# CHARGING.net
KiCad netlist of a schematic drawn in Altium Designer
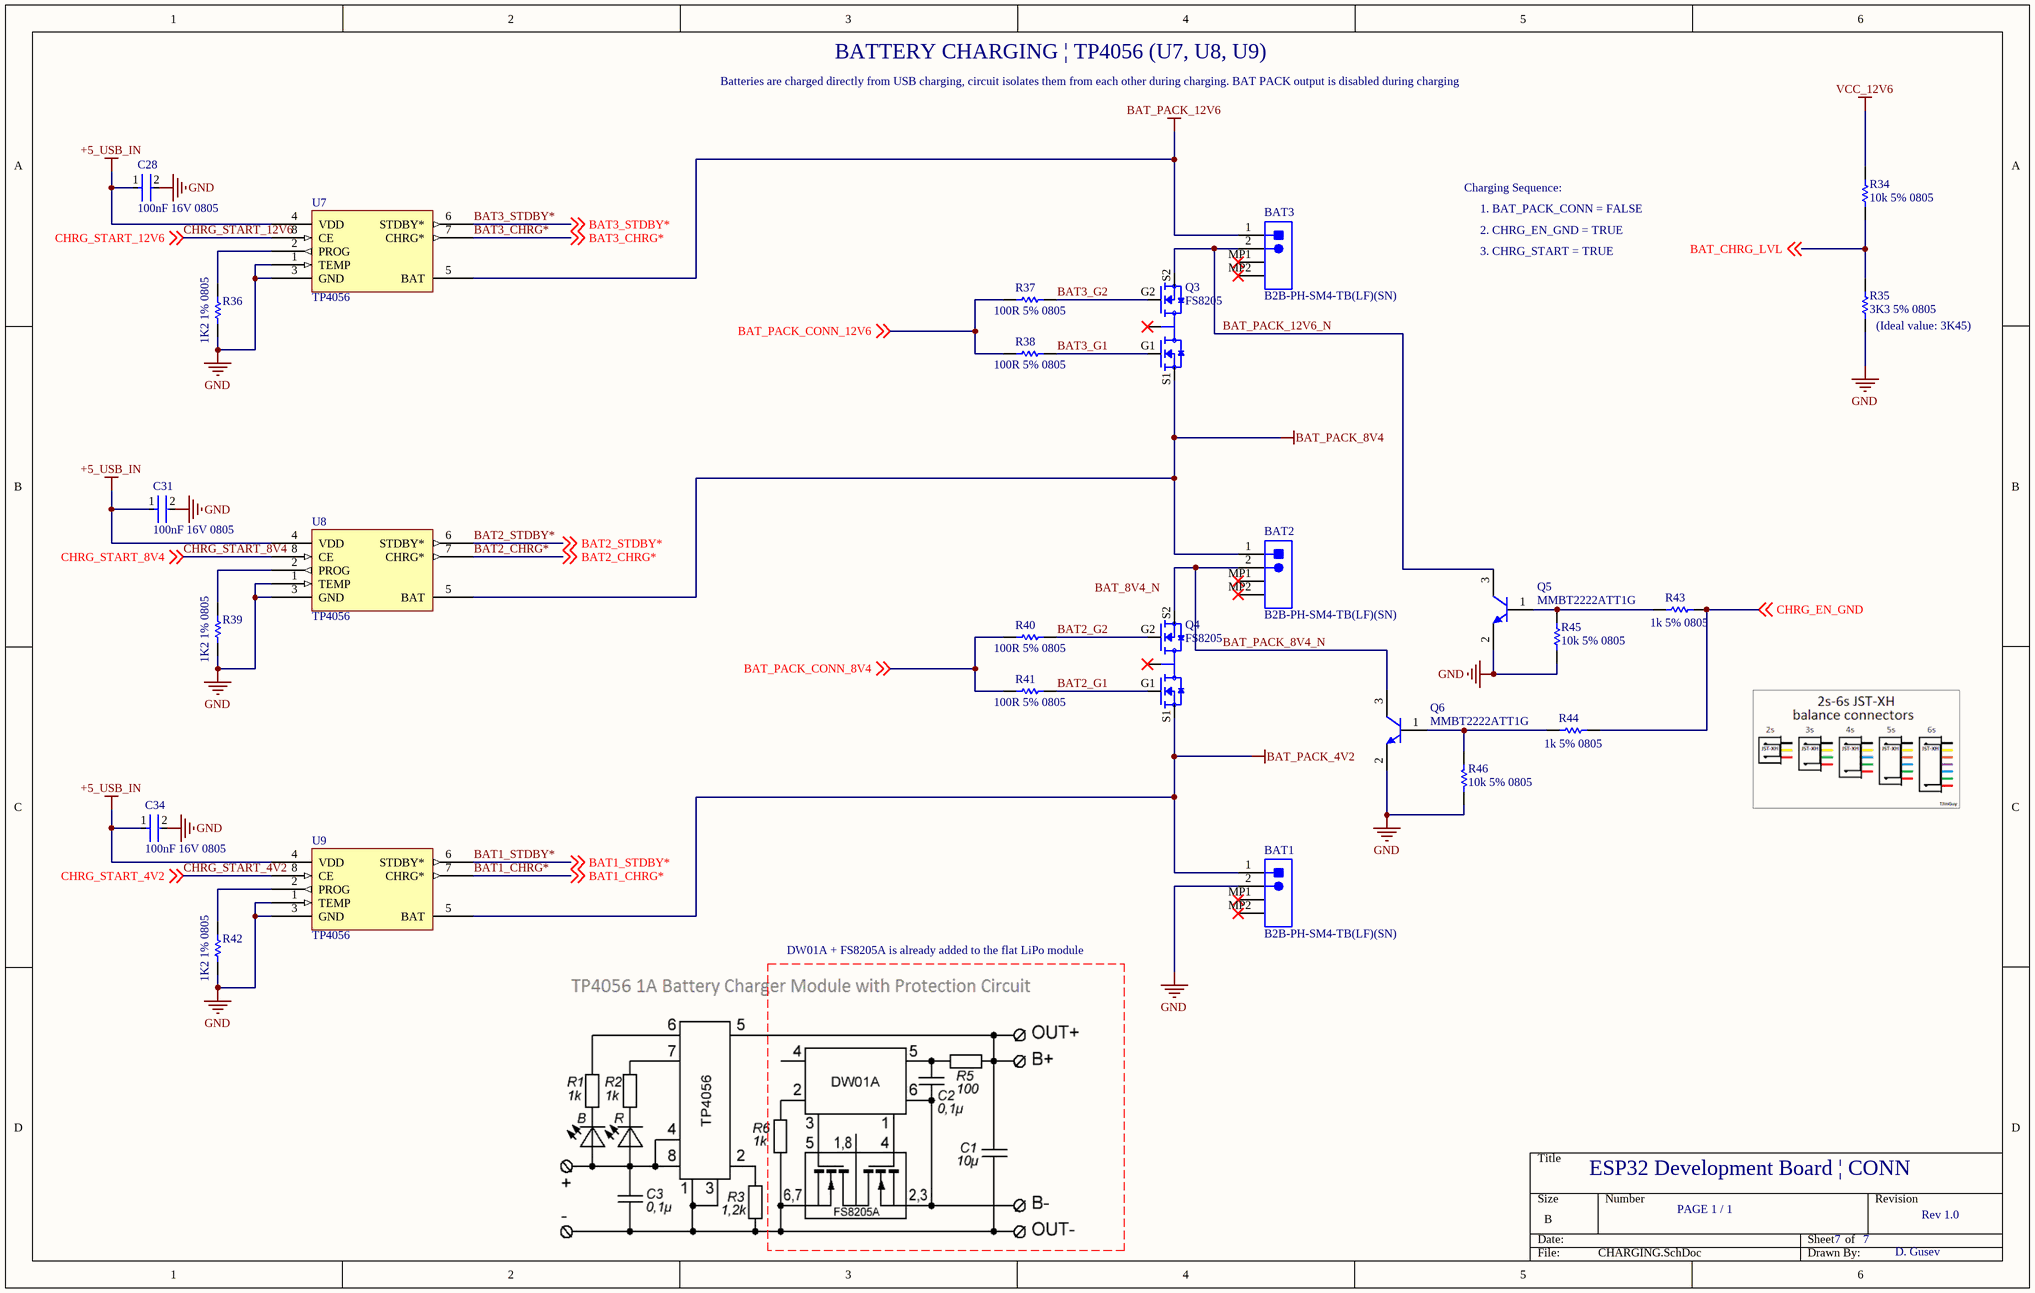
[diagram p0: CHARGING.SchDoc]

(export (version "E")
  (design (tool "Eeschema 10.0.6"))
  (components
    (comp (ref "BAT1")
      (value "B2B-PH-SM4-TB(LF)(SN)")
      (footprint "JST-B2B-PH-SM4-TB-2_V")
      (description "Male Header, Pitch 2 mm, 1 x 2 Position, Height 6.6 mm, RoHS, Tape and Reel")
      (fields (field (name "MANUFACTURER") "JST"))
      (libsource (lib "Altium Content Vault") (part "CN-1P-2M-R2"))
    )
    (comp (ref "BAT2")
      (value "B2B-PH-SM4-TB(LF)(SN)")
      (footprint "JST-B2B-PH-SM4-TB-2_V")
      (description "Male Header, Pitch 2 mm, 1 x 2 Position, Height 6.6 mm, RoHS, Tape and Reel")
      (fields (field (name "MANUFACTURER") "JST"))
      (libsource (lib "Altium Content Vault") (part "CN-1P-2M-R2"))
    )
    (comp (ref "BAT3")
      (value "B2B-PH-SM4-TB(LF)(SN)")
      (footprint "JST-B2B-PH-SM4-TB-2_V")
      (description "Male Header, Pitch 2 mm, 1 x 2 Position, Height 6.6 mm, RoHS, Tape and Reel")
      (fields (field (name "MANUFACTURER") "JST"))
      (libsource (lib "Altium Content Vault") (part "CN-1P-2M-R2"))
    )
    (comp (ref "C28")
      (value "100nF 16V 0805")
      (footprint "FP-C0805C-DN-MFG")
      (description "CAP CER 0.1UF 16V X7R 0805")
      (fields
        (field (name "OCTOPART") "https://octopart.com/c0805c104j4ractu-kemet-12563748")
        (field (name "MANUFACTURER PART NUMBER") "C0805C104J4RACTU")
      )
      (libsource (lib "Altium Content Vault") (part "b4654b650e69147ec39a6b967a45e02"))
    )
    (comp (ref "C31")
      (value "100nF 16V 0805")
      (footprint "FP-C0805C-DN-MFG")
      (description "CAP CER 0.1UF 16V X7R 0805")
      (fields
        (field (name "OCTOPART") "https://octopart.com/c0805c104j4ractu-kemet-12563748")
        (field (name "MANUFACTURER PART NUMBER") "C0805C104J4RACTU")
      )
      (libsource (lib "Altium Content Vault") (part "b4654b650e69147ec39a6b967a45e02"))
    )
    (comp (ref "C34")
      (value "100nF 16V 0805")
      (footprint "FP-C0805C-DN-MFG")
      (description "CAP CER 0.1UF 16V X7R 0805")
      (fields
        (field (name "OCTOPART") "https://octopart.com/c0805c104j4ractu-kemet-12563748")
        (field (name "MANUFACTURER PART NUMBER") "C0805C104J4RACTU")
      )
      (libsource (lib "Altium Content Vault") (part "b4654b650e69147ec39a6b967a45e02"))
    )
    (comp (ref "Q3")
      (value "FS8205")
      (footprint "FS8205")
      (description "Dual N-Channel Enhancement Mode Power MOSFET")
      (fields (field (name "MF") "Fortune Semiconductor"))
      (libsource (lib "ddrlegobrick") (part "FS8205"))
    )
    (comp (ref "Q4")
      (value "FS8205")
      (footprint "FS8205")
      (description "Dual N-Channel Enhancement Mode Power MOSFET")
      (fields (field (name "MF") "Fortune Semiconductor"))
      (libsource (lib "ddrlegobrick") (part "FS8205"))
    )
    (comp (ref "Q5")
      (value "MMBT2222ATT1G")
      (footprint "ONSC-SC-75-3-463-01_V")
      (description "General Purpose Transistor, NPN Silicon, 3-Pin SC-75, Pb-Free, Tape and Reel")
      (fields (field (name "MANUFACTURER") "On Semiconductor"))
      (libsource (lib "Altium Content Vault") (part "ONSC-NPN-B1E2C3-3"))
    )
    (comp (ref "Q6")
      (value "MMBT2222ATT1G")
      (footprint "ONSC-SC-75-3-463-01_V")
      (description "General Purpose Transistor, NPN Silicon, 3-Pin SC-75, Pb-Free, Tape and Reel")
      (fields (field (name "MANUFACTURER") "On Semiconductor"))
      (libsource (lib "Altium Content Vault") (part "ONSC-NPN-B1E2C3-3"))
    )
    (comp (ref "R34")
      (value "10k 5% 0805")
      (footprint "RESC2013X60X35NL10T20")
      (description "Chip Resistor, 10 KOhm, +/- 1%, 0.125 W, -55 to 155 degC, 0805 (2012 Metric), RoHS, Tape and Reel")
      (fields (field (name "MANUFACTURER") "Yageo"))
      (libsource (lib "Altium Content Vault") (part "RES-2"))
    )
    (comp (ref "R35")
      (value "3K3 5% 0805")
      (footprint "RESC2013X60X35ML10T20")
      (description "Chip Resistor, 3.3 KOhm, +/- 1%, 0.125 W, -55 to 155 degC, 0805 (2012 Metric), RoHS, Tape and Reel")
      (fields (field (name "TOLERANCE") "1%") (field (name "MANUFACTURER") "Yageo"))
      (libsource (lib "Altium Content Vault") (part "RES-2"))
    )
    (comp (ref "R36")
      (value "1K2 1% 0805")
      (footprint "RESC2013X70X40ML20T20")
      (fields (field (name "MANUFACTURER") "Panasonic") (field (name "PART NUMBER") "ERJ6ENF1201V"))
      (libsource (lib "Altium Content Vault") (part "RES"))
    )
    (comp (ref "R37")
      (value "100R 5% 0805")
      (footprint "RESC2013X60X35ML10T20")
      (description "Chip Resistor, 100 Ohm, +/-1%, 0.125 W, -55 to 155 degC, 0805 (2012 Metric), RoHS, Tape and Reel")
      (fields (field (name "TOLERANCE") "1%") (field (name "MANUFACTURER") "Yageo"))
      (libsource (lib "Altium Content Vault") (part "RES-2"))
    )
    (comp (ref "R38")
      (value "100R 5% 0805")
      (footprint "RESC2013X60X35ML10T20")
      (description "Chip Resistor, 100 Ohm, +/-1%, 0.125 W, -55 to 155 degC, 0805 (2012 Metric), RoHS, Tape and Reel")
      (fields (field (name "TOLERANCE") "1%") (field (name "MANUFACTURER") "Yageo"))
      (libsource (lib "Altium Content Vault") (part "RES-2"))
    )
    (comp (ref "R39")
      (value "1K2 1% 0805")
      (footprint "RESC2013X70X40ML20T20")
      (fields (field (name "MANUFACTURER") "Panasonic") (field (name "PART NUMBER") "ERJ6ENF1201V"))
      (libsource (lib "Altium Content Vault") (part "RES"))
    )
    (comp (ref "R40")
      (value "100R 5% 0805")
      (footprint "RESC2013X60X35ML10T20")
      (description "Chip Resistor, 100 Ohm, +/-1%, 0.125 W, -55 to 155 degC, 0805 (2012 Metric), RoHS, Tape and Reel")
      (fields (field (name "TOLERANCE") "1%") (field (name "MANUFACTURER") "Yageo"))
      (libsource (lib "Altium Content Vault") (part "RES-2"))
    )
    (comp (ref "R41")
      (value "100R 5% 0805")
      (footprint "RESC2013X60X35ML10T20")
      (description "Chip Resistor, 100 Ohm, +/-1%, 0.125 W, -55 to 155 degC, 0805 (2012 Metric), RoHS, Tape and Reel")
      (fields (field (name "TOLERANCE") "1%") (field (name "MANUFACTURER") "Yageo"))
      (libsource (lib "Altium Content Vault") (part "RES-2"))
    )
    (comp (ref "R42")
      (value "1K2 1% 0805")
      (footprint "RESC2013X70X40ML20T20")
      (fields (field (name "MANUFACTURER") "Panasonic") (field (name "PART NUMBER") "ERJ6ENF1201V"))
      (libsource (lib "Altium Content Vault") (part "RES"))
    )
    (comp (ref "R43")
      (value "1k 5% 0805")
      (footprint "RESC2013X60X35ML10T20")
      (description "Chip Resistor, 1 KOhm, +/- 1%, 125 mW, -55 to 155 degC, 0805 (2012 Metric), RoHS, Tape and Reel")
      (fields (field (name "TOLERANCE") "1%") (field (name "MANUFACTURER") "Yageo"))
      (libsource (lib "Altium Content Vault") (part "RES-2"))
    )
    (comp (ref "R44")
      (value "1k 5% 0805")
      (footprint "RESC2013X60X35ML10T20")
      (description "Chip Resistor, 1 KOhm, +/- 1%, 125 mW, -55 to 155 degC, 0805 (2012 Metric), RoHS, Tape and Reel")
      (fields (field (name "TOLERANCE") "1%") (field (name "MANUFACTURER") "Yageo"))
      (libsource (lib "Altium Content Vault") (part "RES-2"))
    )
    (comp (ref "R45")
      (value "10k 5% 0805")
      (footprint "RESC2013X60X35NL10T20")
      (description "Chip Resistor, 10 KOhm, +/- 1%, 0.125 W, -55 to 155 degC, 0805 (2012 Metric), RoHS, Tape and Reel")
      (fields (field (name "MANUFACTURER") "Yageo"))
      (libsource (lib "Altium Content Vault") (part "RES-2"))
    )
    (comp (ref "R46")
      (value "10k 5% 0805")
      (footprint "RESC2013X60X35NL10T20")
      (description "Chip Resistor, 10 KOhm, +/- 1%, 0.125 W, -55 to 155 degC, 0805 (2012 Metric), RoHS, Tape and Reel")
      (fields (field (name "MANUFACTURER") "Yageo"))
      (libsource (lib "Altium Content Vault") (part "RES-2"))
    )
    (comp (ref "U7")
      (value "TP4056")
      (footprint "TP4056")
      (description "1-CELL LI+ BATTERY CHARGER")
      (libsource (lib "ddrlegobrick") (part "TP4056"))
    )
    (comp (ref "U8")
      (value "TP4056")
      (footprint "TP4056")
      (description "1-CELL LI+ BATTERY CHARGER")
      (libsource (lib "ddrlegobrick") (part "TP4056"))
    )
    (comp (ref "U9")
      (value "TP4056")
      (footprint "TP4056")
      (description "1-CELL LI+ BATTERY CHARGER")
      (libsource (lib "ddrlegobrick") (part "TP4056"))
    )
  )
  (nets
    (net (code "1") (name "+5_USB_IN") (class "Default")
      (node (ref "C28") (pin "1") (pinfunction "1_1") (pintype "passive"))
      (node (ref "C31") (pin "1") (pinfunction "1_1") (pintype "passive"))
      (node (ref "C34") (pin "1") (pinfunction "1_1") (pintype "passive"))
      (node (ref "U7") (pin "4") (pinfunction "VDD_4") (pintype "power_in"))
      (node (ref "U8") (pin "4") (pinfunction "VDD_4") (pintype "power_in"))
      (node (ref "U9") (pin "4") (pinfunction "VDD_4") (pintype "power_in"))
    )
    (net (code "2") (name "/BAT2_G1") (class "Default")
      (node (ref "Q4") (pin "G1") (pinfunction "G1_G1") (pintype "passive"))
      (node (ref "R41") (pin "2") (pinfunction "2_2") (pintype "passive"))
    )
    (net (code "3") (name "/BAT2_G2") (class "Default")
      (node (ref "Q4") (pin "G2") (pinfunction "G2_G2") (pintype "passive"))
      (node (ref "R40") (pin "2") (pinfunction "2_2") (pintype "passive"))
    )
    (net (code "4") (name "/BAT3_G1") (class "Default")
      (node (ref "Q3") (pin "G1") (pinfunction "G1_G1") (pintype "passive"))
      (node (ref "R38") (pin "2") (pinfunction "2_2") (pintype "passive"))
    )
    (net (code "5") (name "/BAT3_G2") (class "Default")
      (node (ref "Q3") (pin "G2") (pinfunction "G2_G2") (pintype "passive"))
      (node (ref "R37") (pin "2") (pinfunction "2_2") (pintype "passive"))
    )
    (net (code "7") (name "/BAT_PACK_8V4_N") (class "Default")
      (node (ref "BAT2") (pin "2") (pinfunction "2_2") (pintype "passive"))
      (node (ref "Q4") (pin "S2") (pinfunction "S2_S2") (pintype "passive"))
      (node (ref "Q6") (pin "3") (pinfunction "C_3") (pintype "passive"))
    )
    (net (code "8") (name "/BAT_PACK_12V6_N") (class "Default")
      (node (ref "BAT3") (pin "2") (pinfunction "2_2") (pintype "passive"))
      (node (ref "Q3") (pin "S2") (pinfunction "S2_S2") (pintype "passive"))
      (node (ref "Q5") (pin "3") (pinfunction "C_3") (pintype "passive"))
    )
    (net (code "9") (name "BAT1_CHRG*") (class "Default")
      (node (ref "U9") (pin "7") (pinfunction "CHRG*_7") (pintype "output"))
    )
    (net (code "10") (name "BAT1_STDBY*") (class "Default")
      (node (ref "U9") (pin "6") (pinfunction "STDBY*_6") (pintype "output"))
    )
    (net (code "11") (name "BAT2_CHRG*") (class "Default")
      (node (ref "U8") (pin "7") (pinfunction "CHRG*_7") (pintype "output"))
    )
    (net (code "12") (name "BAT2_STDBY*") (class "Default")
      (node (ref "U8") (pin "6") (pinfunction "STDBY*_6") (pintype "output"))
    )
    (net (code "13") (name "BAT3_CHRG*") (class "Default")
      (node (ref "U7") (pin "7") (pinfunction "CHRG*_7") (pintype "output"))
    )
    (net (code "14") (name "BAT3_STDBY*") (class "Default")
      (node (ref "U7") (pin "6") (pinfunction "STDBY*_6") (pintype "output"))
    )
    (net (code "15") (name "BAT_CHRG_LVL") (class "Default")
      (node (ref "R34") (pin "1") (pinfunction "1_1") (pintype "passive"))
      (node (ref "R35") (pin "2") (pinfunction "2_2") (pintype "passive"))
    )
    (net (code "16") (name "BAT_PACK_4V2") (class "Default")
      (node (ref "BAT1") (pin "1") (pinfunction "1_1") (pintype "passive"))
      (node (ref "Q4") (pin "S1") (pinfunction "S1_S1") (pintype "passive"))
      (node (ref "U9") (pin "5") (pinfunction "BAT_5") (pintype "power_in"))
    )
    (net (code "17") (name "BAT_PACK_8V4") (class "Default")
      (node (ref "BAT2") (pin "1") (pinfunction "1_1") (pintype "passive"))
      (node (ref "Q3") (pin "S1") (pinfunction "S1_S1") (pintype "passive"))
      (node (ref "U8") (pin "5") (pinfunction "BAT_5") (pintype "power_in"))
    )
    (net (code "18") (name "BAT_PACK_12V6") (class "Default")
      (node (ref "BAT3") (pin "1") (pinfunction "1_1") (pintype "passive"))
      (node (ref "U7") (pin "5") (pinfunction "BAT_5") (pintype "power_in"))
    )
    (net (code "19") (name "BAT_PACK_CONN_8V4") (class "Default")
      (node (ref "R40") (pin "1") (pinfunction "1_1") (pintype "passive"))
      (node (ref "R41") (pin "1") (pinfunction "1_1") (pintype "passive"))
    )
    (net (code "20") (name "BAT_PACK_CONN_12V6") (class "Default")
      (node (ref "R37") (pin "1") (pinfunction "1_1") (pintype "passive"))
      (node (ref "R38") (pin "1") (pinfunction "1_1") (pintype "passive"))
    )
    (net (code "21") (name "CHRG_EN_GND") (class "Default")
      (node (ref "R43") (pin "2") (pinfunction "2_2") (pintype "passive"))
      (node (ref "R44") (pin "2") (pinfunction "2_2") (pintype "passive"))
    )
    (net (code "22") (name "CHRG_START_4V2") (class "Default")
      (node (ref "U9") (pin "8") (pinfunction "CE_8") (pintype "input"))
    )
    (net (code "23") (name "CHRG_START_8V4") (class "Default")
      (node (ref "U8") (pin "8") (pinfunction "CE_8") (pintype "input"))
    )
    (net (code "24") (name "CHRG_START_12V6") (class "Default")
      (node (ref "U7") (pin "8") (pinfunction "CE_8") (pintype "input"))
    )
    (net (code "25") (name "GND") (class "Default")
      (node (ref "BAT1") (pin "2") (pinfunction "2_2") (pintype "passive"))
      (node (ref "C28") (pin "2") (pinfunction "2_2") (pintype "passive"))
      (node (ref "C31") (pin "2") (pinfunction "2_2") (pintype "passive"))
      (node (ref "C34") (pin "2") (pinfunction "2_2") (pintype "passive"))
      (node (ref "Q5") (pin "2") (pinfunction "E_2") (pintype "passive"))
      (node (ref "Q6") (pin "2") (pinfunction "E_2") (pintype "passive"))
      (node (ref "R35") (pin "1") (pinfunction "1_1") (pintype "passive"))
      (node (ref "R36") (pin "1") (pinfunction "1_1") (pintype "passive"))
      (node (ref "R39") (pin "1") (pinfunction "1_1") (pintype "passive"))
      (node (ref "R42") (pin "1") (pinfunction "1_1") (pintype "passive"))
      (node (ref "R45") (pin "1") (pinfunction "1_1") (pintype "passive"))
      (node (ref "R46") (pin "2") (pinfunction "2_2") (pintype "passive"))
      (node (ref "U7") (pin "1") (pinfunction "TEMP_1") (pintype "input"))
      (node (ref "U7") (pin "3") (pinfunction "GND_3") (pintype "passive"))
      (node (ref "U8") (pin "1") (pinfunction "TEMP_1") (pintype "input"))
      (node (ref "U8") (pin "3") (pinfunction "GND_3") (pintype "passive"))
      (node (ref "U9") (pin "1") (pinfunction "TEMP_1") (pintype "input"))
      (node (ref "U9") (pin "3") (pinfunction "GND_3") (pintype "passive"))
    )
    (net (code "26") (name "Net-(Q5-B)") (class "Default")
      (node (ref "Q5") (pin "1") (pinfunction "B_1") (pintype "passive"))
      (node (ref "R43") (pin "1") (pinfunction "1_1") (pintype "passive"))
      (node (ref "R45") (pin "2") (pinfunction "2_2") (pintype "passive"))
    )
    (net (code "27") (name "Net-(Q6-B)") (class "Default")
      (node (ref "Q6") (pin "1") (pinfunction "B_1") (pintype "passive"))
      (node (ref "R44") (pin "1") (pinfunction "1_1") (pintype "passive"))
      (node (ref "R46") (pin "1") (pinfunction "1_1") (pintype "passive"))
    )
    (net (code "28") (name "Net-(U7-PROG)") (class "Default")
      (node (ref "R36") (pin "2") (pinfunction "2_2") (pintype "passive"))
      (node (ref "U7") (pin "2") (pinfunction "PROG_2") (pintype "output"))
    )
    (net (code "29") (name "Net-(U8-PROG)") (class "Default")
      (node (ref "R39") (pin "2") (pinfunction "2_2") (pintype "passive"))
      (node (ref "U8") (pin "2") (pinfunction "PROG_2") (pintype "output"))
    )
    (net (code "30") (name "Net-(U9-PROG)") (class "Default")
      (node (ref "R42") (pin "2") (pinfunction "2_2") (pintype "passive"))
      (node (ref "U9") (pin "2") (pinfunction "PROG_2") (pintype "output"))
    )
    (net (code "31") (name "VCC_12V6") (class "Default")
      (node (ref "R34") (pin "2") (pinfunction "2_2") (pintype "passive"))
    )
    (net (code "32") (name "unconnected-(BAT1-PadMP1)") (class "Default")
      (node (ref "BAT1") (pin "MP1") (pinfunction "MP1_MP1") (pintype "passive+no_connect"))
    )
    (net (code "33") (name "unconnected-(BAT1-PadMP2)") (class "Default")
      (node (ref "BAT1") (pin "MP2") (pinfunction "MP2_MP2") (pintype "passive+no_connect"))
    )
    (net (code "34") (name "unconnected-(BAT2-PadMP1)") (class "Default")
      (node (ref "BAT2") (pin "MP1") (pinfunction "MP1_MP1") (pintype "passive+no_connect"))
    )
    (net (code "35") (name "unconnected-(BAT2-PadMP2)") (class "Default")
      (node (ref "BAT2") (pin "MP2") (pinfunction "MP2_MP2") (pintype "passive+no_connect"))
    )
    (net (code "36") (name "unconnected-(BAT3-PadMP1)") (class "Default")
      (node (ref "BAT3") (pin "MP1") (pinfunction "MP1_MP1") (pintype "passive+no_connect"))
    )
    (net (code "37") (name "unconnected-(BAT3-PadMP2)") (class "Default")
      (node (ref "BAT3") (pin "MP2") (pinfunction "MP2_MP2") (pintype "passive+no_connect"))
    )
    (net (code "38") (name "unconnected-(Q3-PadD12)") (class "Default")
      (node (ref "Q3") (pin "D12") (pinfunction "D12_D12") (pintype "passive+no_connect"))
    )
    (net (code "39") (name "unconnected-(Q4-PadD12)") (class "Default")
      (node (ref "Q4") (pin "D12") (pinfunction "D12_D12") (pintype "passive+no_connect"))
    )
  )
)
